# fpga-bank0.net
KiCad netlist of a schematic drawn in Altium Designer
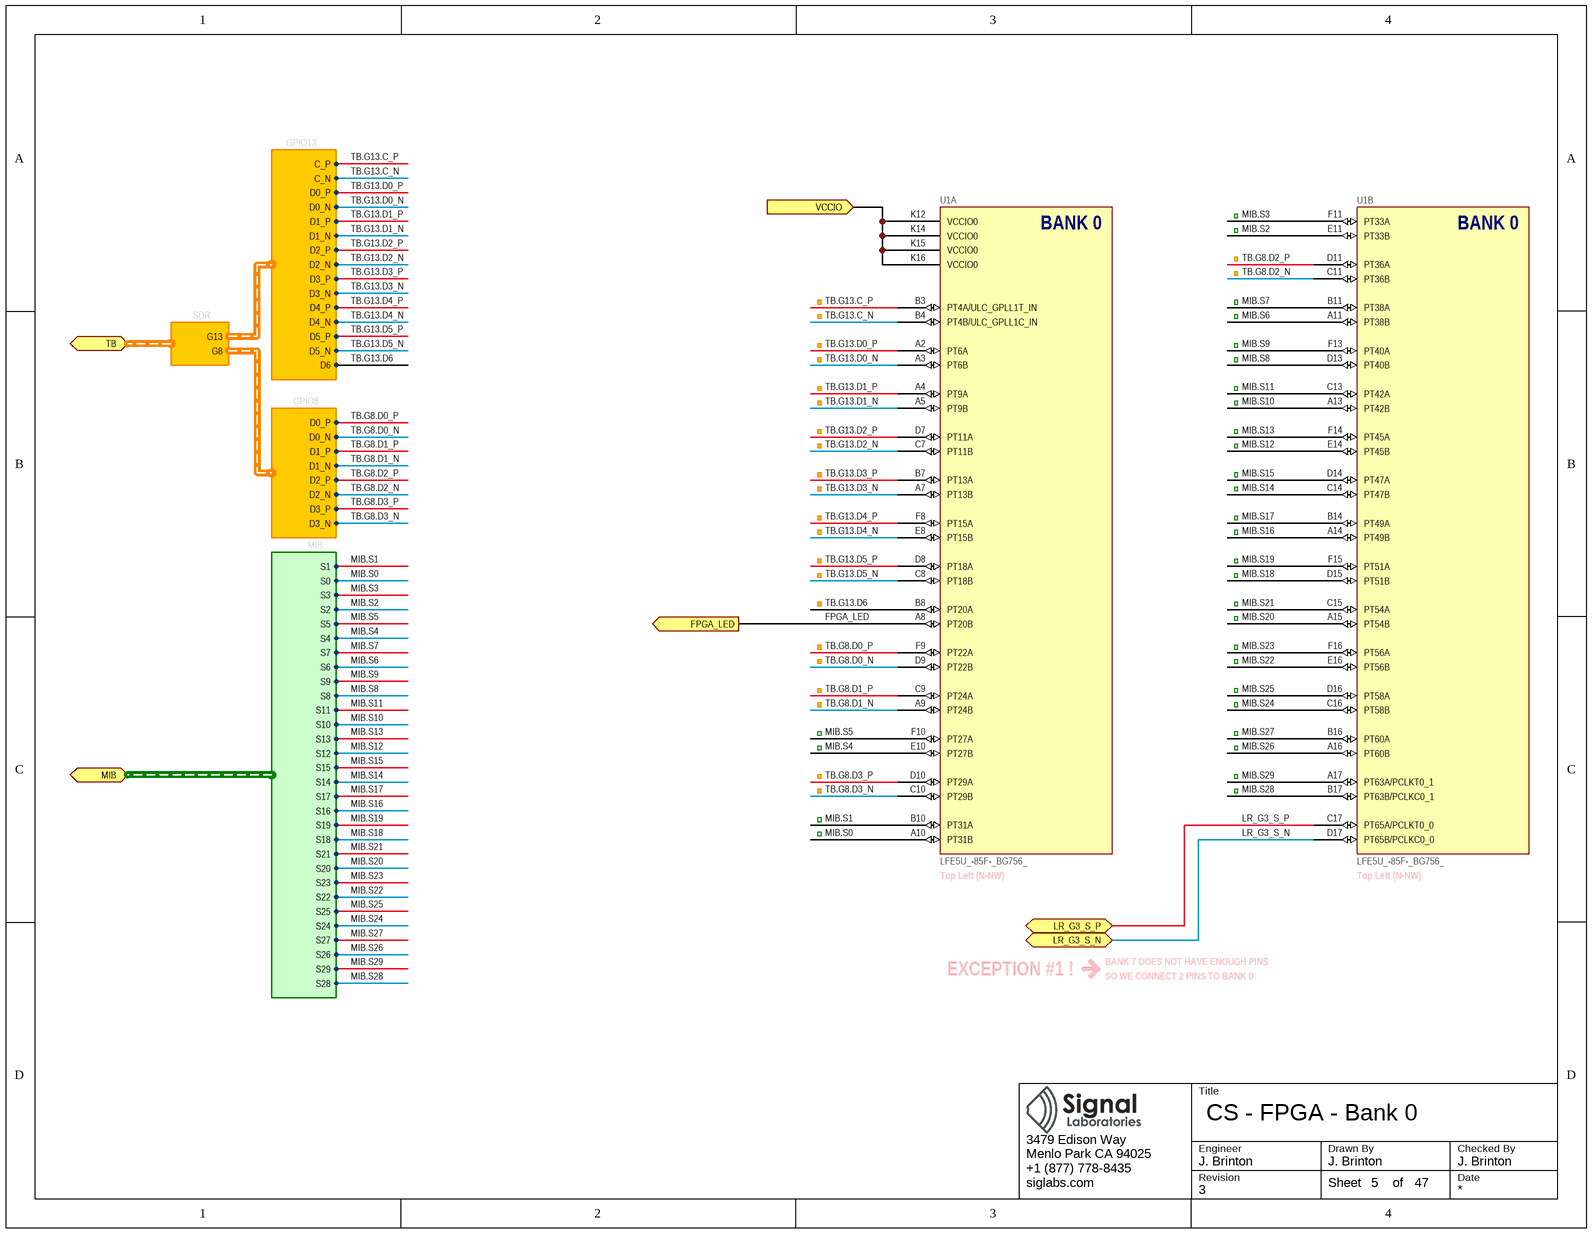
[diagram p0: fpga-bank0.SchDoc]

(export (version "E")
  (design (tool "Eeschema 10.0.6"))
  (components
    (comp (ref "U1")
      (value "LFE5U_-85F-_BG756_")
      (footprint "lattice:caBGA756")
      (description "ECP5 FPGA, 85k LUT, 756-caBGA")
      (fields (field (name "MANUFACTURER") "Lattice Semiconductor"))
      (libsource (lib "lattice") (part "LFE5U_-85F-_BG756_"))
    )
  )
  (nets
    (net (code "4") (name "/FPGA_LED") (class "Default")
      (node (ref "U1") (pin "A8") (pinfunction "PT20B_A8") (pintype "bidirectional"))
    )
    (net (code "5") (name "/LR_G3_S_N") (class "Default")
      (node (ref "U1") (pin "D17") (pinfunction "PT65B/PCLKC0_0_D17") (pintype "bidirectional"))
    )
    (net (code "6") (name "/LR_G3_S_P") (class "Default")
      (node (ref "U1") (pin "C17") (pinfunction "PT65A/PCLKT0_0_C17") (pintype "bidirectional"))
    )
    (net (code "7") (name "/MIB.S0") (class "Default")
      (node (ref "U1") (pin "A10") (pinfunction "PT31B_A10") (pintype "bidirectional"))
    )
    (net (code "8") (name "/MIB.S1") (class "Default")
      (node (ref "U1") (pin "B10") (pinfunction "PT31A_B10") (pintype "bidirectional"))
    )
    (net (code "9") (name "/MIB.S2") (class "Default")
      (node (ref "U1") (pin "E11") (pinfunction "PT33B_E11") (pintype "bidirectional"))
    )
    (net (code "10") (name "/MIB.S3") (class "Default")
      (node (ref "U1") (pin "F11") (pinfunction "PT33A_F11") (pintype "bidirectional"))
    )
    (net (code "11") (name "/MIB.S4") (class "Default")
      (node (ref "U1") (pin "E10") (pinfunction "PT27B_E10") (pintype "bidirectional"))
    )
    (net (code "12") (name "/MIB.S5") (class "Default")
      (node (ref "U1") (pin "F10") (pinfunction "PT27A_F10") (pintype "bidirectional"))
    )
    (net (code "13") (name "/MIB.S6") (class "Default")
      (node (ref "U1") (pin "A11") (pinfunction "PT38B_A11") (pintype "bidirectional"))
    )
    (net (code "14") (name "/MIB.S7") (class "Default")
      (node (ref "U1") (pin "B11") (pinfunction "PT38A_B11") (pintype "bidirectional"))
    )
    (net (code "15") (name "/MIB.S8") (class "Default")
      (node (ref "U1") (pin "D13") (pinfunction "PT40B_D13") (pintype "bidirectional"))
    )
    (net (code "16") (name "/MIB.S9") (class "Default")
      (node (ref "U1") (pin "F13") (pinfunction "PT40A_F13") (pintype "bidirectional"))
    )
    (net (code "17") (name "/MIB.S10") (class "Default")
      (node (ref "U1") (pin "A13") (pinfunction "PT42B_A13") (pintype "bidirectional"))
    )
    (net (code "18") (name "/MIB.S11") (class "Default")
      (node (ref "U1") (pin "C13") (pinfunction "PT42A_C13") (pintype "bidirectional"))
    )
    (net (code "19") (name "/MIB.S12") (class "Default")
      (node (ref "U1") (pin "E14") (pinfunction "PT45B_E14") (pintype "bidirectional"))
    )
    (net (code "20") (name "/MIB.S13") (class "Default")
      (node (ref "U1") (pin "F14") (pinfunction "PT45A_F14") (pintype "bidirectional"))
    )
    (net (code "21") (name "/MIB.S14") (class "Default")
      (node (ref "U1") (pin "C14") (pinfunction "PT47B_C14") (pintype "bidirectional"))
    )
    (net (code "22") (name "/MIB.S15") (class "Default")
      (node (ref "U1") (pin "D14") (pinfunction "PT47A_D14") (pintype "bidirectional"))
    )
    (net (code "23") (name "/MIB.S16") (class "Default")
      (node (ref "U1") (pin "A14") (pinfunction "PT49B_A14") (pintype "bidirectional"))
    )
    (net (code "24") (name "/MIB.S17") (class "Default")
      (node (ref "U1") (pin "B14") (pinfunction "PT49A_B14") (pintype "bidirectional"))
    )
    (net (code "25") (name "/MIB.S18") (class "Default")
      (node (ref "U1") (pin "D15") (pinfunction "PT51B_D15") (pintype "bidirectional"))
    )
    (net (code "26") (name "/MIB.S19") (class "Default")
      (node (ref "U1") (pin "F15") (pinfunction "PT51A_F15") (pintype "bidirectional"))
    )
    (net (code "27") (name "/MIB.S20") (class "Default")
      (node (ref "U1") (pin "A15") (pinfunction "PT54B_A15") (pintype "bidirectional"))
    )
    (net (code "28") (name "/MIB.S21") (class "Default")
      (node (ref "U1") (pin "C15") (pinfunction "PT54A_C15") (pintype "bidirectional"))
    )
    (net (code "29") (name "/MIB.S22") (class "Default")
      (node (ref "U1") (pin "E16") (pinfunction "PT56B_E16") (pintype "bidirectional"))
    )
    (net (code "30") (name "/MIB.S23") (class "Default")
      (node (ref "U1") (pin "F16") (pinfunction "PT56A_F16") (pintype "bidirectional"))
    )
    (net (code "31") (name "/MIB.S24") (class "Default")
      (node (ref "U1") (pin "C16") (pinfunction "PT58B_C16") (pintype "bidirectional"))
    )
    (net (code "32") (name "/MIB.S25") (class "Default")
      (node (ref "U1") (pin "D16") (pinfunction "PT58A_D16") (pintype "bidirectional"))
    )
    (net (code "33") (name "/MIB.S26") (class "Default")
      (node (ref "U1") (pin "A16") (pinfunction "PT60B_A16") (pintype "bidirectional"))
    )
    (net (code "34") (name "/MIB.S27") (class "Default")
      (node (ref "U1") (pin "B16") (pinfunction "PT60A_B16") (pintype "bidirectional"))
    )
    (net (code "35") (name "/MIB.S28") (class "Default")
      (node (ref "U1") (pin "B17") (pinfunction "PT63B/PCLKC0_1_B17") (pintype "bidirectional"))
    )
    (net (code "36") (name "/MIB.S29") (class "Default")
      (node (ref "U1") (pin "A17") (pinfunction "PT63A/PCLKT0_1_A17") (pintype "bidirectional"))
    )
    (net (code "37") (name "/TB.G8.D0_N") (class "Default")
      (node (ref "U1") (pin "D9") (pinfunction "PT22B_D9") (pintype "bidirectional"))
    )
    (net (code "38") (name "/TB.G8.D0_P") (class "Default")
      (node (ref "U1") (pin "F9") (pinfunction "PT22A_F9") (pintype "bidirectional"))
    )
    (net (code "39") (name "/TB.G8.D1_N") (class "Default")
      (node (ref "U1") (pin "A9") (pinfunction "PT24B_A9") (pintype "bidirectional"))
    )
    (net (code "40") (name "/TB.G8.D1_P") (class "Default")
      (node (ref "U1") (pin "C9") (pinfunction "PT24A_C9") (pintype "bidirectional"))
    )
    (net (code "41") (name "/TB.G8.D2_N") (class "Default")
      (node (ref "U1") (pin "C11") (pinfunction "PT36B_C11") (pintype "bidirectional"))
    )
    (net (code "42") (name "/TB.G8.D2_P") (class "Default")
      (node (ref "U1") (pin "D11") (pinfunction "PT36A_D11") (pintype "bidirectional"))
    )
    (net (code "43") (name "/TB.G8.D3_N") (class "Default")
      (node (ref "U1") (pin "C10") (pinfunction "PT29B_C10") (pintype "bidirectional"))
    )
    (net (code "44") (name "/TB.G8.D3_P") (class "Default")
      (node (ref "U1") (pin "D10") (pinfunction "PT29A_D10") (pintype "bidirectional"))
    )
    (net (code "45") (name "/TB.G13.C_N") (class "Default")
      (node (ref "U1") (pin "B4") (pinfunction "PT4B/ULC_GPLL1C_IN_B4") (pintype "bidirectional"))
    )
    (net (code "46") (name "/TB.G13.C_P") (class "Default")
      (node (ref "U1") (pin "B3") (pinfunction "PT4A/ULC_GPLL1T_IN_B3") (pintype "bidirectional"))
    )
    (net (code "47") (name "/TB.G13.D0_N") (class "Default")
      (node (ref "U1") (pin "A3") (pinfunction "PT6B_A3") (pintype "bidirectional"))
    )
    (net (code "48") (name "/TB.G13.D0_P") (class "Default")
      (node (ref "U1") (pin "A2") (pinfunction "PT6A_A2") (pintype "bidirectional"))
    )
    (net (code "49") (name "/TB.G13.D1_N") (class "Default")
      (node (ref "U1") (pin "A5") (pinfunction "PT9B_A5") (pintype "bidirectional"))
    )
    (net (code "50") (name "/TB.G13.D1_P") (class "Default")
      (node (ref "U1") (pin "A4") (pinfunction "PT9A_A4") (pintype "bidirectional"))
    )
    (net (code "51") (name "/TB.G13.D2_N") (class "Default")
      (node (ref "U1") (pin "C7") (pinfunction "PT11B_C7") (pintype "bidirectional"))
    )
    (net (code "52") (name "/TB.G13.D2_P") (class "Default")
      (node (ref "U1") (pin "D7") (pinfunction "PT11A_D7") (pintype "bidirectional"))
    )
    (net (code "53") (name "/TB.G13.D3_N") (class "Default")
      (node (ref "U1") (pin "A7") (pinfunction "PT13B_A7") (pintype "bidirectional"))
    )
    (net (code "54") (name "/TB.G13.D3_P") (class "Default")
      (node (ref "U1") (pin "B7") (pinfunction "PT13A_B7") (pintype "bidirectional"))
    )
    (net (code "55") (name "/TB.G13.D4_N") (class "Default")
      (node (ref "U1") (pin "E8") (pinfunction "PT15B_E8") (pintype "bidirectional"))
    )
    (net (code "56") (name "/TB.G13.D4_P") (class "Default")
      (node (ref "U1") (pin "F8") (pinfunction "PT15A_F8") (pintype "bidirectional"))
    )
    (net (code "57") (name "/TB.G13.D5_N") (class "Default")
      (node (ref "U1") (pin "C8") (pinfunction "PT18B_C8") (pintype "bidirectional"))
    )
    (net (code "58") (name "/TB.G13.D5_P") (class "Default")
      (node (ref "U1") (pin "D8") (pinfunction "PT18A_D8") (pintype "bidirectional"))
    )
    (net (code "59") (name "/TB.G13.D6") (class "Default")
      (node (ref "U1") (pin "B8") (pinfunction "PT20A_B8") (pintype "bidirectional"))
    )
    (net (code "61") (name "/VCCIO") (class "Default")
      (node (ref "U1") (pin "K12") (pinfunction "VCCIO0_K12") (pintype "power_in"))
      (node (ref "U1") (pin "K14") (pinfunction "VCCIO0_K14") (pintype "power_in"))
      (node (ref "U1") (pin "K15") (pinfunction "VCCIO0_K15") (pintype "power_in"))
      (node (ref "U1") (pin "K16") (pinfunction "VCCIO0_K16") (pintype "power_in"))
    )
  )
)
